# HCP_Single_Ended.net
KiCad netlist of a schematic drawn in Altium Designer
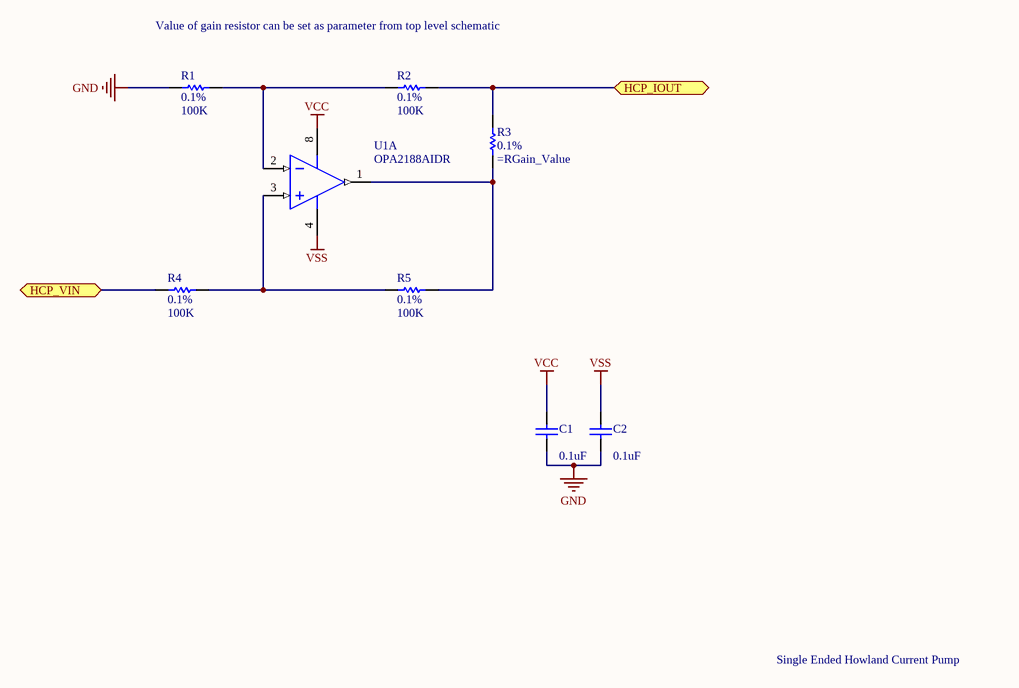
[diagram p0: HCP_Single_Ended.SchDoc]

(export (version "E")
  (design (tool "Eeschema 10.0.6"))
  (components
    (comp (ref "C1")
      (value "0.1uF")
      (footprint "1608[0603]")
      (description "Capacitor (Semiconductor SIM Model)")
      (fields (field (name "Comment") "Cap Semi") (field (name "PUBLISHER") "Altium Limited"))
      (libsource (lib "Miscellaneous Devices") (part "Cap Semi"))
    )
    (comp (ref "C2")
      (value "0.1uF")
      (footprint "1608[0603]")
      (description "Capacitor (Semiconductor SIM Model)")
      (fields (field (name "Comment") "Cap Semi") (field (name "PUBLISHER") "Altium Limited"))
      (libsource (lib "Miscellaneous Devices") (part "Cap Semi"))
    )
    (comp (ref "R1")
      (value "0.1%")
      (footprint "6-0805_M")
      (description "Resistor")
      (fields (field (name "ALTIUM_VALUE") "100K") (field (name "PUBLISHER") "Altium Limited"))
      (libsource (lib "Miscellaneous Devices") (part "Res1"))
    )
    (comp (ref "R2")
      (value "0.1%")
      (footprint "6-0805_M")
      (description "Resistor")
      (fields (field (name "ALTIUM_VALUE") "100K") (field (name "PUBLISHER") "Altium Limited"))
      (libsource (lib "Miscellaneous Devices") (part "Res1"))
    )
    (comp (ref "R3")
      (value "0.1%")
      (footprint "6-0805_M")
      (description "Resistor")
      (fields (field (name "PUBLISHER") "Altium Limited"))
      (libsource (lib "Miscellaneous Devices") (part "Res1"))
    )
    (comp (ref "R4")
      (value "0.1%")
      (footprint "6-0805_M")
      (description "Resistor")
      (fields (field (name "ALTIUM_VALUE") "100K") (field (name "PUBLISHER") "Altium Limited"))
      (libsource (lib "Miscellaneous Devices") (part "Res1"))
    )
    (comp (ref "R5")
      (value "0.1%")
      (footprint "6-0805_M")
      (description "Resistor")
      (fields (field (name "ALTIUM_VALUE") "100K") (field (name "PUBLISHER") "Altium Limited"))
      (libsource (lib "Miscellaneous Devices") (part "Res1"))
    )
    (comp (ref "U1")
      (value "OPA2188AIDR")
      (footprint "D0008A_L")
      (fields (field (name "MANUFACTURER") "Texas Instruments"))
      (libsource (lib "Altium Content Vault") (part "TI-OPA-8_2"))
    )
  )
  (nets
    (net (code "1") (name "/HCP_IOUT") (class "Default")
      (node (ref "R2") (pin "2") (pinfunction "2_2") (pintype "passive"))
      (node (ref "R3") (pin "2") (pinfunction "2_2") (pintype "passive"))
    )
    (net (code "2") (name "/HCP_VIN") (class "Default")
      (node (ref "R4") (pin "1") (pinfunction "1_1") (pintype "passive"))
    )
    (net (code "3") (name "GND") (class "Default")
      (node (ref "C1") (pin "1") (pinfunction "1_1") (pintype "passive"))
      (node (ref "C2") (pin "1") (pinfunction "1_1") (pintype "passive"))
      (node (ref "R1") (pin "1") (pinfunction "1_1") (pintype "passive"))
    )
    (net (code "4") (name "Net-(U1A-IN_A+)") (class "Default")
      (node (ref "R4") (pin "2") (pinfunction "2_2") (pintype "passive"))
      (node (ref "R5") (pin "1") (pinfunction "1_1") (pintype "passive"))
      (node (ref "U1") (pin "3") (pinfunction "IN_A+_3") (pintype "input"))
    )
    (net (code "5") (name "Net-(U1A-IN_A-)") (class "Default")
      (node (ref "R1") (pin "2") (pinfunction "2_2") (pintype "passive"))
      (node (ref "R2") (pin "1") (pinfunction "1_1") (pintype "passive"))
      (node (ref "U1") (pin "2") (pinfunction "IN_A-_2") (pintype "input"))
    )
    (net (code "6") (name "Net-(U1A-OUT_A)") (class "Default")
      (node (ref "R3") (pin "1") (pinfunction "1_1") (pintype "passive"))
      (node (ref "R5") (pin "2") (pinfunction "2_2") (pintype "passive"))
      (node (ref "U1") (pin "1") (pinfunction "OUT_A_1") (pintype "output"))
    )
    (net (code "7") (name "VCC") (class "Default")
      (node (ref "C1") (pin "2") (pinfunction "2_2") (pintype "passive"))
      (node (ref "U1") (pin "8") (pinfunction "V+_8") (pintype "power_in"))
    )
    (net (code "8") (name "VSS") (class "Default")
      (node (ref "C2") (pin "2") (pinfunction "2_2") (pintype "passive"))
      (node (ref "U1") (pin "4") (pinfunction "V-_4") (pintype "power_in"))
    )
  )
)
